# vusbtiny_version.net
KiCad netlist of a schematic drawn in EAGLE
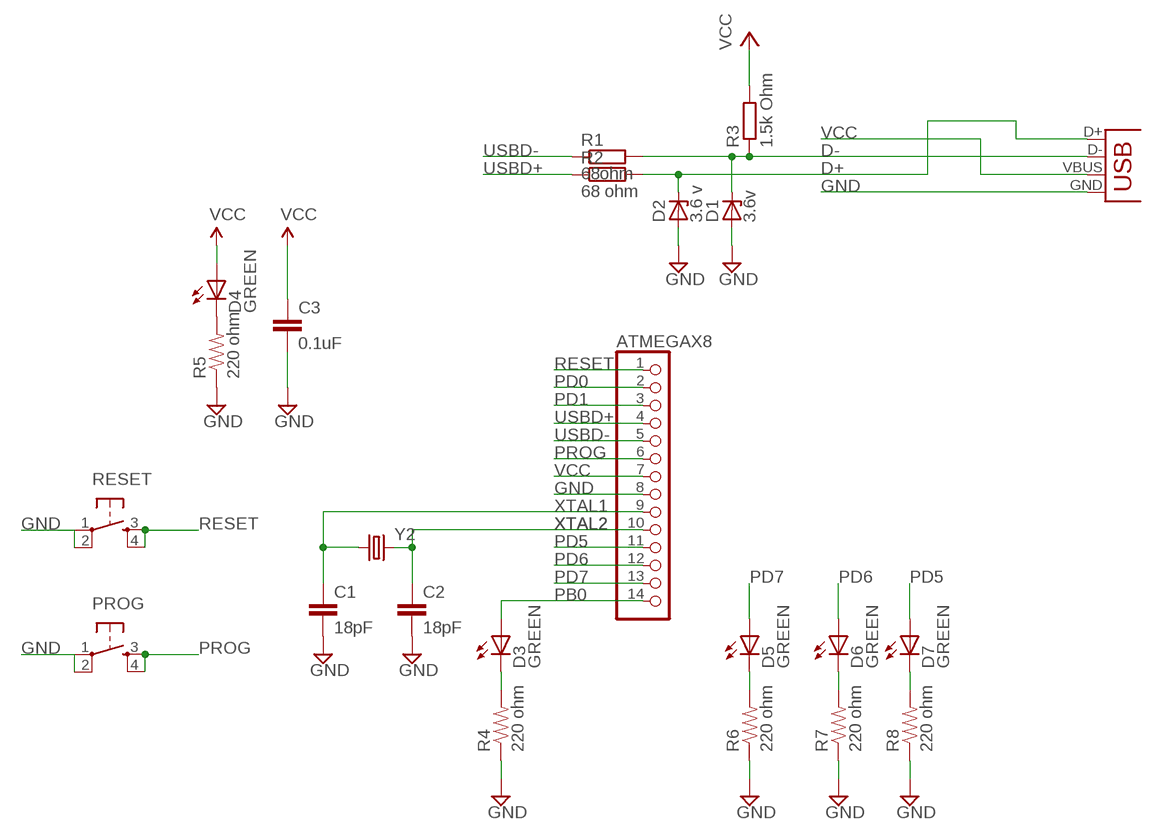
[diagram p0: schematic, sheet 1]

(export (version "E")
  (design (tool "Eeschema 10.0.6"))
  (components
    (comp (ref "ATMEGAX8")
      (value "PINHD-1X14")
      (footprint "eagle-import:1X14")
      (libsource (lib "eagle-import") (part "PINHD-1X14"))
    )
    (comp (ref "C1")
      (value "18pF")
      (footprint "eagle-import:1206")
      (libsource (lib "eagle-import") (part "CAP1206"))
    )
    (comp (ref "C2")
      (value "18pF")
      (footprint "eagle-import:1206")
      (libsource (lib "eagle-import") (part "CAP1206"))
    )
    (comp (ref "C3")
      (value "0.1uF")
      (footprint "eagle-import:1206")
      (libsource (lib "eagle-import") (part "CAP1206"))
    )
    (comp (ref "D1")
      (value "3.6v")
      (footprint "eagle-import:SOT23")
      (libsource (lib "eagle-import") (part "ZENER-DIODESOT23"))
    )
    (comp (ref "D2")
      (value "3.6 v")
      (footprint "eagle-import:SOT23")
      (libsource (lib "eagle-import") (part "ZENER-DIODESOT23"))
    )
    (comp (ref "D3")
      (value "GREEN")
      (footprint "eagle-import:LED-1206")
      (libsource (lib "eagle-import") (part "LED-GREENLARGE"))
    )
    (comp (ref "D4")
      (value "GREEN")
      (footprint "eagle-import:LED-1206")
      (libsource (lib "eagle-import") (part "LED-GREENLARGE"))
    )
    (comp (ref "D5")
      (value "GREEN")
      (footprint "eagle-import:LED-1206")
      (libsource (lib "eagle-import") (part "LED-GREENLARGE"))
    )
    (comp (ref "D6")
      (value "GREEN")
      (footprint "eagle-import:LED-1206")
      (libsource (lib "eagle-import") (part "LED-GREENLARGE"))
    )
    (comp (ref "D7")
      (value "GREEN")
      (footprint "eagle-import:LED-1206")
      (libsource (lib "eagle-import") (part "LED-GREENLARGE"))
    )
    (comp (ref "JP1")
      (value "USBSMD")
      (footprint "eagle-import:USB-MINIB")
      (libsource (lib "eagle-import") (part "USBSMD"))
    )
    (comp (ref "PROG")
      (value "TAC_SWITCHPTH")
      (footprint "eagle-import:TACTILE-PTH")
      (libsource (lib "eagle-import") (part "TAC_SWITCHPTH"))
    )
    (comp (ref "R1")
      (value "68ohm")
      (footprint "eagle-import:R0805")
      (libsource (lib "eagle-import") (part "R-EU_R0805"))
    )
    (comp (ref "R2")
      (value "68 ohm")
      (footprint "eagle-import:R0805")
      (libsource (lib "eagle-import") (part "R-EU_R0805"))
    )
    (comp (ref "R3")
      (value "1.5k Ohm")
      (footprint "eagle-import:R1206")
      (libsource (lib "eagle-import") (part "R-EU_R1206"))
    )
    (comp (ref "R4")
      (value "220 ohm")
      (footprint "eagle-import:1206")
      (libsource (lib "eagle-import") (part "RESISTOR1206"))
    )
    (comp (ref "R5")
      (value "220 ohm")
      (footprint "eagle-import:1206")
      (libsource (lib "eagle-import") (part "RESISTOR1206"))
    )
    (comp (ref "R6")
      (value "220 ohm")
      (footprint "eagle-import:1206")
      (libsource (lib "eagle-import") (part "RESISTOR1206"))
    )
    (comp (ref "R7")
      (value "220 ohm")
      (footprint "eagle-import:1206")
      (libsource (lib "eagle-import") (part "RESISTOR1206"))
    )
    (comp (ref "R8")
      (value "220 ohm")
      (footprint "eagle-import:1206")
      (libsource (lib "eagle-import") (part "RESISTOR1206"))
    )
    (comp (ref "RESET")
      (value "TAC_SWITCHPTH")
      (footprint "eagle-import:TACTILE-PTH")
      (libsource (lib "eagle-import") (part "TAC_SWITCHPTH"))
    )
    (comp (ref "Y2")
      (value "CRYSTALHC49US")
      (footprint "eagle-import:HC49US")
      (libsource (lib "eagle-import") (part "CRYSTALHC49US"))
    )
  )
  (nets
    (net (code "1") (name "/D+") (class "Default")
      (node (ref "D2") (pin "3") (pinfunction "C_3") (pintype "passive"))
      (node (ref "JP1") (pin "D+") (pinfunction "D+_D+") (pintype "bidirectional"))
      (node (ref "R2") (pin "2") (pinfunction "2_2") (pintype "passive"))
    )
    (net (code "2") (name "/D-") (class "Default")
      (node (ref "D1") (pin "3") (pinfunction "C_3") (pintype "passive"))
      (node (ref "JP1") (pin "D-") (pinfunction "D-_D-") (pintype "bidirectional"))
      (node (ref "R1") (pin "2") (pinfunction "2_2") (pintype "passive"))
      (node (ref "R3") (pin "1") (pinfunction "1_1") (pintype "passive"))
    )
    (net (code "3") (name "/PB0") (class "Default")
      (node (ref "ATMEGAX8") (pin "14") (pinfunction "14_14") (pintype "passive"))
      (node (ref "D3") (pin "A") (pinfunction "A_A") (pintype "passive"))
    )
    (net (code "4") (name "/PD0") (class "Default")
      (node (ref "ATMEGAX8") (pin "2") (pinfunction "2_2") (pintype "passive"))
    )
    (net (code "5") (name "/PD1") (class "Default")
      (node (ref "ATMEGAX8") (pin "3") (pinfunction "3_3") (pintype "passive"))
    )
    (net (code "6") (name "/PD5") (class "Default")
      (node (ref "ATMEGAX8") (pin "11") (pinfunction "11_11") (pintype "passive"))
      (node (ref "D7") (pin "A") (pinfunction "A_A") (pintype "passive"))
    )
    (net (code "7") (name "/PD6") (class "Default")
      (node (ref "ATMEGAX8") (pin "12") (pinfunction "12_12") (pintype "passive"))
      (node (ref "D6") (pin "A") (pinfunction "A_A") (pintype "passive"))
    )
    (net (code "8") (name "/PD7") (class "Default")
      (node (ref "ATMEGAX8") (pin "13") (pinfunction "13_13") (pintype "passive"))
      (node (ref "D5") (pin "A") (pinfunction "A_A") (pintype "passive"))
    )
    (net (code "9") (name "/PROG") (class "Default")
      (node (ref "ATMEGAX8") (pin "6") (pinfunction "6_6") (pintype "passive"))
      (node (ref "PROG") (pin "3") (pinfunction "3_3") (pintype "passive"))
      (node (ref "PROG") (pin "4") (pinfunction "4_4") (pintype "passive"))
    )
    (net (code "10") (name "/RESET") (class "Default")
      (node (ref "ATMEGAX8") (pin "1") (pinfunction "1_1") (pintype "passive"))
      (node (ref "RESET") (pin "3") (pinfunction "3_3") (pintype "passive"))
      (node (ref "RESET") (pin "4") (pinfunction "4_4") (pintype "passive"))
    )
    (net (code "11") (name "/USBD+") (class "Default")
      (node (ref "ATMEGAX8") (pin "4") (pinfunction "4_4") (pintype "passive"))
      (node (ref "R2") (pin "1") (pinfunction "1_1") (pintype "passive"))
    )
    (net (code "12") (name "/USBD-") (class "Default")
      (node (ref "ATMEGAX8") (pin "5") (pinfunction "5_5") (pintype "passive"))
      (node (ref "R1") (pin "1") (pinfunction "1_1") (pintype "passive"))
    )
    (net (code "13") (name "/XTAL1") (class "Default")
      (node (ref "ATMEGAX8") (pin "9") (pinfunction "9_9") (pintype "passive"))
      (node (ref "C1") (pin "1") (pinfunction "1_1") (pintype "passive"))
      (node (ref "Y2") (pin "1") (pinfunction "1_1") (pintype "passive"))
    )
    (net (code "14") (name "/XTAL2") (class "Default")
      (node (ref "ATMEGAX8") (pin "10") (pinfunction "10_10") (pintype "passive"))
      (node (ref "C2") (pin "1") (pinfunction "1_1") (pintype "passive"))
      (node (ref "Y2") (pin "2") (pinfunction "2_2") (pintype "passive"))
    )
    (net (code "15") (name "GND") (class "Default")
      (node (ref "ATMEGAX8") (pin "8") (pinfunction "8_8") (pintype "passive"))
      (node (ref "C1") (pin "2") (pinfunction "2_2") (pintype "passive"))
      (node (ref "C2") (pin "2") (pinfunction "2_2") (pintype "passive"))
      (node (ref "C3") (pin "2") (pinfunction "2_2") (pintype "passive"))
      (node (ref "D1") (pin "1") (pinfunction "A_1") (pintype "passive"))
      (node (ref "D2") (pin "1") (pinfunction "A_1") (pintype "passive"))
      (node (ref "JP1") (pin "GND") (pinfunction "GND_GND") (pintype "bidirectional"))
      (node (ref "PROG") (pin "1") (pinfunction "1_1") (pintype "passive"))
      (node (ref "PROG") (pin "2") (pinfunction "2_2") (pintype "passive"))
      (node (ref "R4") (pin "1") (pinfunction "1_1") (pintype "passive"))
      (node (ref "R5") (pin "1") (pinfunction "1_1") (pintype "passive"))
      (node (ref "R6") (pin "1") (pinfunction "1_1") (pintype "passive"))
      (node (ref "R7") (pin "1") (pinfunction "1_1") (pintype "passive"))
      (node (ref "R8") (pin "1") (pinfunction "1_1") (pintype "passive"))
      (node (ref "RESET") (pin "1") (pinfunction "1_1") (pintype "passive"))
      (node (ref "RESET") (pin "2") (pinfunction "2_2") (pintype "passive"))
    )
    (net (code "16") (name "Net-(D3-PadC)") (class "Default")
      (node (ref "D3") (pin "C") (pinfunction "C_C") (pintype "passive"))
      (node (ref "R4") (pin "2") (pinfunction "2_2") (pintype "passive"))
    )
    (net (code "17") (name "Net-(D4-PadC)") (class "Default")
      (node (ref "D4") (pin "C") (pinfunction "C_C") (pintype "passive"))
      (node (ref "R5") (pin "2") (pinfunction "2_2") (pintype "passive"))
    )
    (net (code "18") (name "Net-(D5-PadC)") (class "Default")
      (node (ref "D5") (pin "C") (pinfunction "C_C") (pintype "passive"))
      (node (ref "R6") (pin "2") (pinfunction "2_2") (pintype "passive"))
    )
    (net (code "19") (name "Net-(D6-PadC)") (class "Default")
      (node (ref "D6") (pin "C") (pinfunction "C_C") (pintype "passive"))
      (node (ref "R7") (pin "2") (pinfunction "2_2") (pintype "passive"))
    )
    (net (code "20") (name "Net-(D7-PadC)") (class "Default")
      (node (ref "D7") (pin "C") (pinfunction "C_C") (pintype "passive"))
      (node (ref "R8") (pin "2") (pinfunction "2_2") (pintype "passive"))
    )
    (net (code "21") (name "VCC") (class "Default")
      (node (ref "ATMEGAX8") (pin "7") (pinfunction "7_7") (pintype "passive"))
      (node (ref "C3") (pin "1") (pinfunction "1_1") (pintype "passive"))
      (node (ref "D4") (pin "A") (pinfunction "A_A") (pintype "passive"))
      (node (ref "JP1") (pin "VBUS") (pinfunction "VBUS_VBUS") (pintype "bidirectional"))
      (node (ref "R3") (pin "2") (pinfunction "2_2") (pintype "passive"))
    )
  )
)
